# Mailchecker2.net
KiCad netlist of a schematic drawn in EAGLE
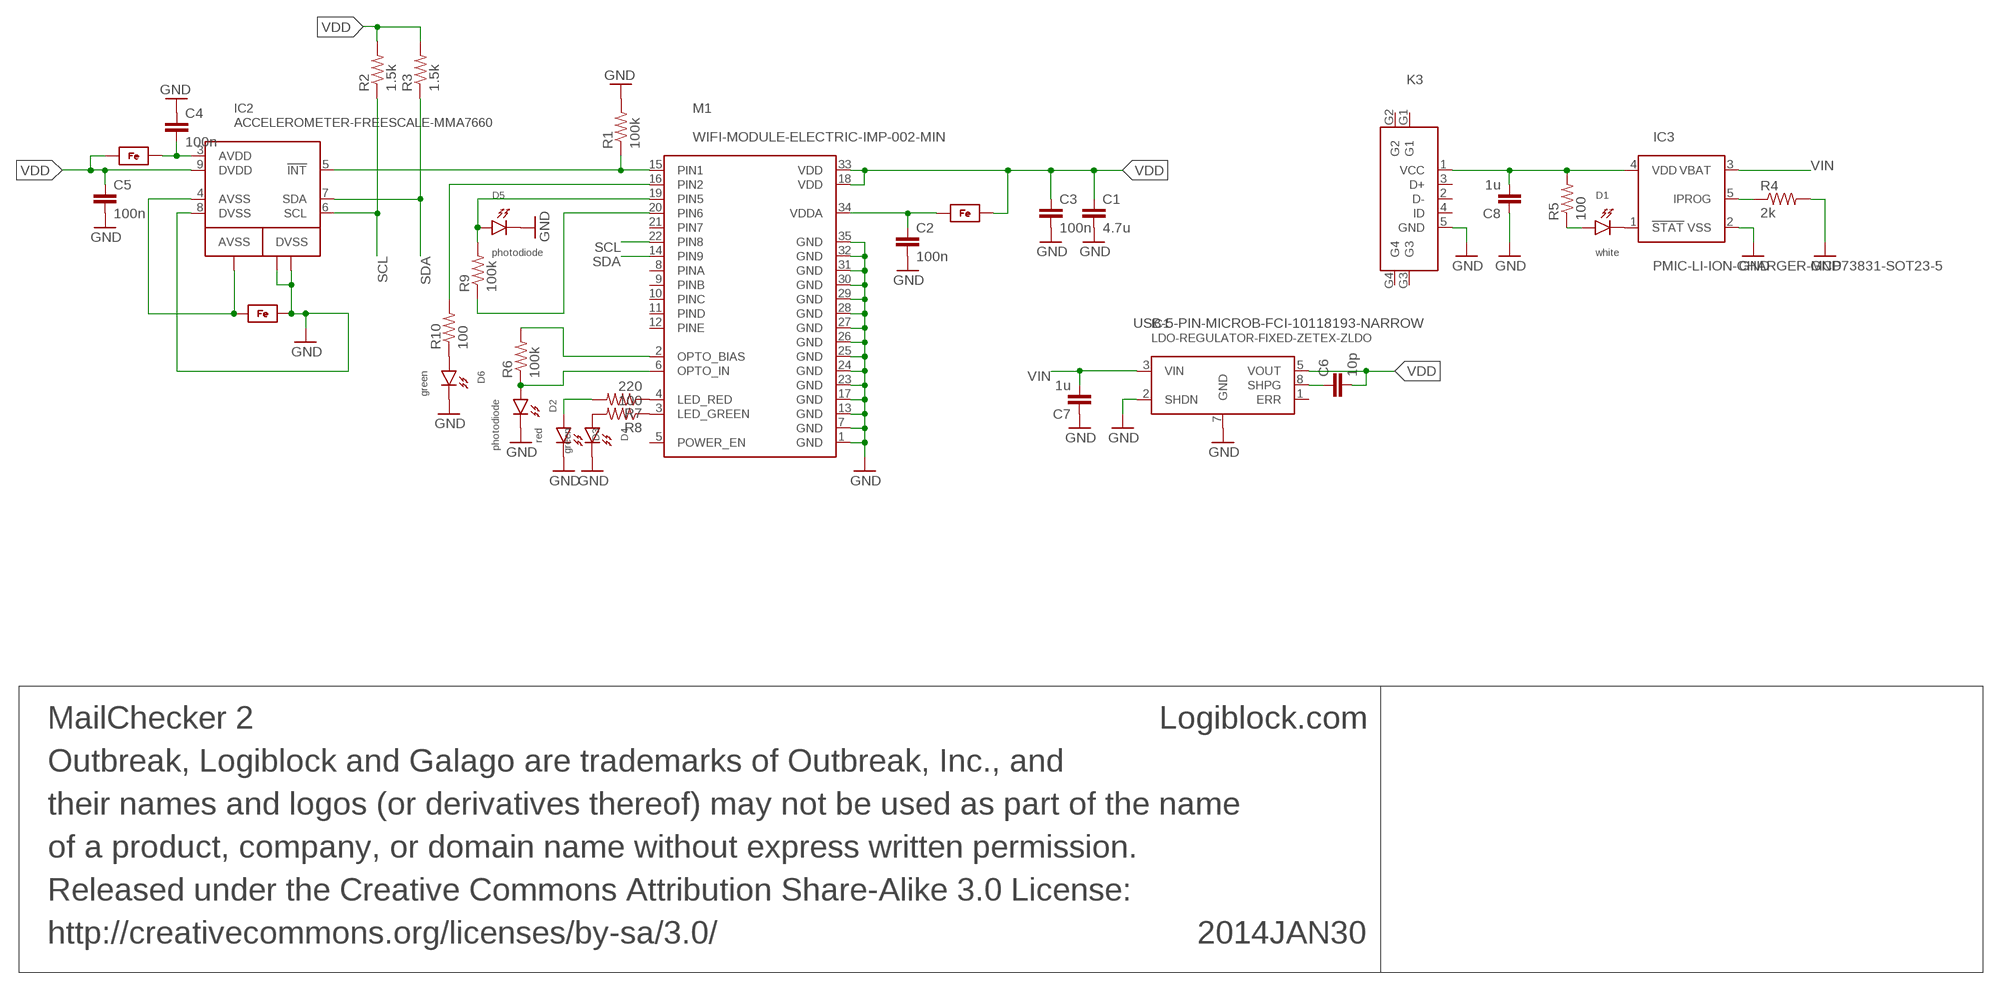
[diagram p0: schematic, sheet 1]

(export (version "E")
  (design (tool "Eeschema 10.0.6"))
  (components
    (comp (ref "2014JAN30")
      (value "MailChecker 2")
      (footprint "eagle-import:INFO-BLOCK")
      (libsource (lib "eagle-import") (part "INFO-BLOCK"))
    )
    (comp (ref "C1")
      (value "4.7u")
      (footprint "eagle-import:0805-MIN")
      (libsource (lib "eagle-import") (part "CAP-0805-MIN"))
    )
    (comp (ref "C2")
      (value "100n")
      (footprint "eagle-import:0402-MIN")
      (libsource (lib "eagle-import") (part "CAP-0402-MIN"))
    )
    (comp (ref "C3")
      (value "100n")
      (footprint "eagle-import:0402-MIN")
      (libsource (lib "eagle-import") (part "CAP-0402-MIN"))
    )
    (comp (ref "C4")
      (value "100n")
      (footprint "eagle-import:0402-MIN")
      (libsource (lib "eagle-import") (part "CAP-0402-MIN"))
    )
    (comp (ref "C5")
      (value "100n")
      (footprint "eagle-import:0402-MIN")
      (libsource (lib "eagle-import") (part "CAP-0402-MIN"))
    )
    (comp (ref "C6")
      (value "10p")
      (footprint "eagle-import:0402-MIN")
      (libsource (lib "eagle-import") (part "CAP-0402-MIN"))
    )
    (comp (ref "C7")
      (value "1u")
      (footprint "eagle-import:0603-MIN")
      (libsource (lib "eagle-import") (part "CAP-0603-MIN"))
    )
    (comp (ref "C8")
      (value "1u")
      (footprint "eagle-import:0603-MIN")
      (libsource (lib "eagle-import") (part "CAP-0603-MIN"))
    )
    (comp (ref "D1")
      (value "white")
      (footprint "eagle-import:0603-DIODE-MIN")
      (libsource (lib "eagle-import") (part "LED-0603-MIN"))
    )
    (comp (ref "D2")
      (value "photodiode")
      (footprint "eagle-import:0603-DIODE-MIN")
      (libsource (lib "eagle-import") (part "LED-0603-MIN"))
    )
    (comp (ref "D3")
      (value "red")
      (footprint "eagle-import:0603-DIODE-MIN")
      (libsource (lib "eagle-import") (part "LED-0603-MIN"))
    )
    (comp (ref "D4")
      (value "green")
      (footprint "eagle-import:0603-DIODE-MIN")
      (libsource (lib "eagle-import") (part "LED-0603-MIN"))
    )
    (comp (ref "D5")
      (value "photodiode")
      (footprint "eagle-import:0603-DIODE-MIN")
      (libsource (lib "eagle-import") (part "LED-0603-MIN"))
    )
    (comp (ref "D6")
      (value "green")
      (footprint "eagle-import:0603-DIODE-MIN")
      (libsource (lib "eagle-import") (part "LED-0603-MIN"))
    )
    (comp (ref "FB1")
      (value "FERRITE-BEAD-0603-MIN")
      (footprint "eagle-import:0603-MIN")
      (libsource (lib "eagle-import") (part "FERRITE-BEAD-0603-MIN"))
    )
    (comp (ref "FB2")
      (value "FERRITE-BEAD-0603-MIN")
      (footprint "eagle-import:0603-MIN")
      (libsource (lib "eagle-import") (part "FERRITE-BEAD-0603-MIN"))
    )
    (comp (ref "FB3")
      (value "FERRITE-BEAD-0603-MIN")
      (footprint "eagle-import:0603-MIN")
      (libsource (lib "eagle-import") (part "FERRITE-BEAD-0603-MIN"))
    )
    (comp (ref "IC1")
      (value "LDO-REGULATOR-FIXED-ZETEX-ZLDO")
      (footprint "eagle-import:SM8-ZETEX")
      (libsource (lib "eagle-import") (part "LDO-REGULATOR-FIXED-ZETEX-ZLDO"))
    )
    (comp (ref "IC2")
      (value "ACCELEROMETER-FREESCALE-MMA7660")
      (footprint "eagle-import:QFN10-3X3MM-FREESCALE-MMA7660")
      (libsource (lib "eagle-import") (part "ACCELEROMETER-FREESCALE-MMA7660"))
    )
    (comp (ref "IC3")
      (value "PMIC-LI-ION-CHARGER-MCP73831-SOT23-5")
      (footprint "eagle-import:SOT23-5")
      (libsource (lib "eagle-import") (part "PMIC-LI-ION-CHARGER-MCP73831-SOT23-5"))
    )
    (comp (ref "K3")
      (value "USB-5-PIN-MICROB-FCI-10118193-NARROW")
      (footprint "eagle-import:USB-MICROB-FCI-10118193-NARROW")
      (libsource (lib "eagle-import") (part "USB-5-PIN-MICROB-FCI-10118193-NARROW"))
    )
    (comp (ref "M1")
      (value "WIFI-MODULE-ELECTRIC-IMP-002-MIN")
      (footprint "eagle-import:ELECTRIC-IMP-002-MIN")
      (libsource (lib "eagle-import") (part "WIFI-MODULE-ELECTRIC-IMP-002-MIN"))
    )
    (comp (ref "R1")
      (value "100k")
      (footprint "eagle-import:0402-MIN")
      (libsource (lib "eagle-import") (part "RESISTOR-0402-MIN"))
    )
    (comp (ref "R2")
      (value "1.5k")
      (footprint "eagle-import:0402-MIN")
      (libsource (lib "eagle-import") (part "RESISTOR-0402-MIN"))
    )
    (comp (ref "R3")
      (value "1.5k")
      (footprint "eagle-import:0402-MIN")
      (libsource (lib "eagle-import") (part "RESISTOR-0402-MIN"))
    )
    (comp (ref "R4")
      (value "2k")
      (footprint "eagle-import:0402-MIN")
      (libsource (lib "eagle-import") (part "RESISTOR-0402-MIN"))
    )
    (comp (ref "R5")
      (value "100")
      (footprint "eagle-import:0402-MIN")
      (libsource (lib "eagle-import") (part "RESISTOR-0402-MIN"))
    )
    (comp (ref "R6")
      (value "100k")
      (footprint "eagle-import:0402-MIN")
      (libsource (lib "eagle-import") (part "RESISTOR-0402-MIN"))
    )
    (comp (ref "R7")
      (value "220")
      (footprint "eagle-import:0402-MIN")
      (libsource (lib "eagle-import") (part "RESISTOR-0402-MIN"))
    )
    (comp (ref "R8")
      (value "100")
      (footprint "eagle-import:0402-MIN")
      (libsource (lib "eagle-import") (part "RESISTOR-0402-MIN"))
    )
    (comp (ref "R9")
      (value "100k")
      (footprint "eagle-import:0402-MIN")
      (libsource (lib "eagle-import") (part "RESISTOR-0402-MIN"))
    )
    (comp (ref "R10")
      (value "100")
      (footprint "eagle-import:0402-MIN")
      (libsource (lib "eagle-import") (part "RESISTOR-0402-MIN"))
    )
  )
  (nets
    (net (code "1") (name "/SCL") (class "Default")
      (node (ref "IC2") (pin "6") (pinfunction "SCL_6") (pintype "bidirectional"))
      (node (ref "M1") (pin "22") (pinfunction "PIN8_22") (pintype "bidirectional"))
      (node (ref "R2") (pin "1") (pinfunction "1_1") (pintype "passive"))
    )
    (net (code "2") (name "/SDA") (class "Default")
      (node (ref "IC2") (pin "7") (pinfunction "SDA_7") (pintype "bidirectional"))
      (node (ref "M1") (pin "14") (pinfunction "PIN9_14") (pintype "bidirectional"))
      (node (ref "R3") (pin "1") (pinfunction "1_1") (pintype "passive"))
    )
    (net (code "3") (name "/VIN") (class "Default")
      (node (ref "C7") (pin "1") (pinfunction "1_1") (pintype "bidirectional"))
      (node (ref "IC1") (pin "3") (pinfunction "VIN_3") (pintype "bidirectional"))
      (node (ref "IC3") (pin "3") (pinfunction "VBAT_3") (pintype "bidirectional"))
    )
    (net (code "4") (name "GND") (class "Default")
      (node (ref "C1") (pin "1") (pinfunction "1_1") (pintype "bidirectional"))
      (node (ref "C2") (pin "1") (pinfunction "1_1") (pintype "bidirectional"))
      (node (ref "C3") (pin "1") (pinfunction "1_1") (pintype "bidirectional"))
      (node (ref "C4") (pin "2") (pinfunction "2_2") (pintype "bidirectional"))
      (node (ref "C5") (pin "1") (pinfunction "1_1") (pintype "bidirectional"))
      (node (ref "C7") (pin "2") (pinfunction "2_2") (pintype "bidirectional"))
      (node (ref "C8") (pin "2") (pinfunction "2_2") (pintype "bidirectional"))
      (node (ref "D2") (pin "K") (pinfunction "K_K") (pintype "bidirectional"))
      (node (ref "D3") (pin "K") (pinfunction "K_K") (pintype "bidirectional"))
      (node (ref "D4") (pin "K") (pinfunction "K_K") (pintype "bidirectional"))
      (node (ref "D5") (pin "K") (pinfunction "K_K") (pintype "bidirectional"))
      (node (ref "D6") (pin "K") (pinfunction "K_K") (pintype "bidirectional"))
      (node (ref "FB2") (pin "2") (pinfunction "2_2") (pintype "bidirectional"))
      (node (ref "IC1") (pin "2") (pinfunction "SHDN_2") (pintype "bidirectional"))
      (node (ref "IC1") (pin "7") (pinfunction "GND_7") (pintype "bidirectional"))
      (node (ref "IC2") (pin "8") (pinfunction "DVSS_8") (pintype "bidirectional"))
      (node (ref "IC2") (pin "G1") (pinfunction "G1_G1") (pintype "bidirectional"))
      (node (ref "IC2") (pin "G2") (pinfunction "G2_G2") (pintype "bidirectional"))
      (node (ref "IC3") (pin "2") (pinfunction "VSS_2") (pintype "bidirectional"))
      (node (ref "K3") (pin "5") (pinfunction "GND_5") (pintype "bidirectional"))
      (node (ref "M1") (pin "1") (pinfunction "GND_1") (pintype "bidirectional"))
      (node (ref "M1") (pin "13") (pinfunction "GND_13") (pintype "bidirectional"))
      (node (ref "M1") (pin "17") (pinfunction "GND_17") (pintype "bidirectional"))
      (node (ref "M1") (pin "23") (pinfunction "GND_23") (pintype "bidirectional"))
      (node (ref "M1") (pin "24") (pinfunction "GND_24") (pintype "bidirectional"))
      (node (ref "M1") (pin "25") (pinfunction "GND_25") (pintype "bidirectional"))
      (node (ref "M1") (pin "26") (pinfunction "GND_26") (pintype "bidirectional"))
      (node (ref "M1") (pin "27") (pinfunction "GND_27") (pintype "bidirectional"))
      (node (ref "M1") (pin "28") (pinfunction "GND_28") (pintype "bidirectional"))
      (node (ref "M1") (pin "29") (pinfunction "GND_29") (pintype "bidirectional"))
      (node (ref "M1") (pin "30") (pinfunction "GND_30") (pintype "bidirectional"))
      (node (ref "M1") (pin "31") (pinfunction "GND_31") (pintype "bidirectional"))
      (node (ref "M1") (pin "32") (pinfunction "GND_32") (pintype "bidirectional"))
      (node (ref "M1") (pin "35") (pinfunction "GND_35") (pintype "bidirectional"))
      (node (ref "M1") (pin "7") (pinfunction "GND_7") (pintype "bidirectional"))
      (node (ref "R1") (pin "2") (pinfunction "2_2") (pintype "passive"))
      (node (ref "R4") (pin "2") (pinfunction "2_2") (pintype "passive"))
    )
    (net (code "5") (name "Net-(D1-PadA)") (class "Default")
      (node (ref "D1") (pin "A") (pinfunction "A_A") (pintype "bidirectional"))
      (node (ref "R5") (pin "1") (pinfunction "1_1") (pintype "passive"))
    )
    (net (code "6") (name "Net-(D3-PadA)") (class "Default")
      (node (ref "D3") (pin "A") (pinfunction "A_A") (pintype "bidirectional"))
      (node (ref "R7") (pin "2") (pinfunction "2_2") (pintype "passive"))
    )
    (net (code "7") (name "Net-(D4-PadA)") (class "Default")
      (node (ref "D4") (pin "A") (pinfunction "A_A") (pintype "bidirectional"))
      (node (ref "R8") (pin "2") (pinfunction "2_2") (pintype "passive"))
    )
    (net (code "8") (name "Net-(D6-PadA)") (class "Default")
      (node (ref "D6") (pin "A") (pinfunction "A_A") (pintype "bidirectional"))
      (node (ref "R10") (pin "1") (pinfunction "1_1") (pintype "passive"))
    )
    (net (code "9") (name "Net-(IC1-SHPG)") (class "Default")
      (node (ref "C6") (pin "2") (pinfunction "2_2") (pintype "bidirectional"))
      (node (ref "IC1") (pin "8") (pinfunction "SHPG_8") (pintype "bidirectional"))
    )
    (net (code "10") (name "Net-(IC2-AVDD)") (class "Default")
      (node (ref "C4") (pin "1") (pinfunction "1_1") (pintype "bidirectional"))
      (node (ref "FB3") (pin "2") (pinfunction "2_2") (pintype "bidirectional"))
      (node (ref "IC2") (pin "3") (pinfunction "AVDD_3") (pintype "bidirectional"))
    )
    (net (code "11") (name "Net-(IC2-AVSS)") (class "Default")
      (node (ref "FB2") (pin "1") (pinfunction "1_1") (pintype "bidirectional"))
      (node (ref "IC2") (pin "1") (pinfunction "G3_1") (pintype "bidirectional"))
      (node (ref "IC2") (pin "4") (pinfunction "AVSS_4") (pintype "bidirectional"))
    )
    (net (code "12") (name "Net-(IC2-~{INT})") (class "Default")
      (node (ref "IC2") (pin "5") (pinfunction "~{INT}_5") (pintype "bidirectional"))
      (node (ref "M1") (pin "15") (pinfunction "PIN1_15") (pintype "bidirectional"))
      (node (ref "R1") (pin "1") (pinfunction "1_1") (pintype "passive"))
    )
    (net (code "13") (name "Net-(IC3-IPROG)") (class "Default")
      (node (ref "IC3") (pin "5") (pinfunction "IPROG_5") (pintype "bidirectional"))
      (node (ref "R4") (pin "1") (pinfunction "1_1") (pintype "passive"))
    )
    (net (code "14") (name "Net-(IC3-VDD)") (class "Default")
      (node (ref "C8") (pin "1") (pinfunction "1_1") (pintype "bidirectional"))
      (node (ref "IC3") (pin "4") (pinfunction "VDD_4") (pintype "bidirectional"))
      (node (ref "K3") (pin "1") (pinfunction "VCC_1") (pintype "bidirectional"))
      (node (ref "R5") (pin "2") (pinfunction "2_2") (pintype "passive"))
    )
    (net (code "15") (name "Net-(IC3-~{STAT})") (class "Default")
      (node (ref "D1") (pin "K") (pinfunction "K_K") (pintype "bidirectional"))
      (node (ref "IC3") (pin "1") (pinfunction "~{STAT}_1") (pintype "bidirectional"))
    )
    (net (code "16") (name "Net-(M1-LED_GREEN)") (class "Default")
      (node (ref "M1") (pin "3") (pinfunction "LED_GREEN_3") (pintype "bidirectional"))
      (node (ref "R8") (pin "1") (pinfunction "1_1") (pintype "passive"))
    )
    (net (code "17") (name "Net-(M1-LED_RED)") (class "Default")
      (node (ref "M1") (pin "4") (pinfunction "LED_RED_4") (pintype "bidirectional"))
      (node (ref "R7") (pin "1") (pinfunction "1_1") (pintype "passive"))
    )
    (net (code "18") (name "Net-(M1-OPTO_BIAS)") (class "Default")
      (node (ref "M1") (pin "2") (pinfunction "OPTO_BIAS_2") (pintype "bidirectional"))
      (node (ref "R6") (pin "2") (pinfunction "2_2") (pintype "passive"))
    )
    (net (code "19") (name "Net-(M1-OPTO_IN)") (class "Default")
      (node (ref "D2") (pin "A") (pinfunction "A_A") (pintype "bidirectional"))
      (node (ref "M1") (pin "6") (pinfunction "OPTO_IN_6") (pintype "bidirectional"))
      (node (ref "R6") (pin "1") (pinfunction "1_1") (pintype "passive"))
    )
    (net (code "20") (name "Net-(M1-PIN2)") (class "Default")
      (node (ref "M1") (pin "16") (pinfunction "PIN2_16") (pintype "bidirectional"))
      (node (ref "R10") (pin "2") (pinfunction "2_2") (pintype "passive"))
    )
    (net (code "21") (name "Net-(M1-PIN5)") (class "Default")
      (node (ref "D5") (pin "A") (pinfunction "A_A") (pintype "bidirectional"))
      (node (ref "M1") (pin "19") (pinfunction "PIN5_19") (pintype "bidirectional"))
      (node (ref "R9") (pin "2") (pinfunction "2_2") (pintype "passive"))
    )
    (net (code "22") (name "Net-(M1-PIN6)") (class "Default")
      (node (ref "M1") (pin "20") (pinfunction "PIN6_20") (pintype "bidirectional"))
      (node (ref "R9") (pin "1") (pinfunction "1_1") (pintype "passive"))
    )
    (net (code "23") (name "Net-(M1-VDDA)") (class "Default")
      (node (ref "C2") (pin "2") (pinfunction "2_2") (pintype "bidirectional"))
      (node (ref "FB1") (pin "1") (pinfunction "1_1") (pintype "bidirectional"))
      (node (ref "M1") (pin "34") (pinfunction "VDDA_34") (pintype "bidirectional"))
    )
    (net (code "24") (name "VDD") (class "Default")
      (node (ref "C1") (pin "2") (pinfunction "2_2") (pintype "bidirectional"))
      (node (ref "C3") (pin "2") (pinfunction "2_2") (pintype "bidirectional"))
      (node (ref "C5") (pin "2") (pinfunction "2_2") (pintype "bidirectional"))
      (node (ref "C6") (pin "1") (pinfunction "1_1") (pintype "bidirectional"))
      (node (ref "FB1") (pin "2") (pinfunction "2_2") (pintype "bidirectional"))
      (node (ref "FB3") (pin "1") (pinfunction "1_1") (pintype "bidirectional"))
      (node (ref "IC1") (pin "5") (pinfunction "VOUT_5") (pintype "bidirectional"))
      (node (ref "IC2") (pin "9") (pinfunction "DVDD_9") (pintype "bidirectional"))
      (node (ref "M1") (pin "18") (pinfunction "VDD_18") (pintype "bidirectional"))
      (node (ref "M1") (pin "33") (pinfunction "VDD_33") (pintype "bidirectional"))
      (node (ref "R2") (pin "2") (pinfunction "2_2") (pintype "passive"))
      (node (ref "R3") (pin "2") (pinfunction "2_2") (pintype "passive"))
    )
    (net (code "25") (name "unconnected-(IC1-ERR-Pad1)") (class "Default")
      (node (ref "IC1") (pin "1") (pinfunction "ERR_1") (pintype "bidirectional"))
    )
    (net (code "26") (name "unconnected-(K3-D+-Pad3)") (class "Default")
      (node (ref "K3") (pin "3") (pinfunction "D+_3") (pintype "bidirectional"))
    )
    (net (code "27") (name "unconnected-(K3-D--Pad2)") (class "Default")
      (node (ref "K3") (pin "2") (pinfunction "D-_2") (pintype "bidirectional"))
    )
    (net (code "28") (name "unconnected-(K3-ID-Pad4)") (class "Default")
      (node (ref "K3") (pin "4") (pinfunction "ID_4") (pintype "bidirectional"))
    )
    (net (code "29") (name "unconnected-(K3-PadG1)") (class "Default")
      (node (ref "K3") (pin "G1") (pinfunction "G1_G1") (pintype "bidirectional"))
    )
    (net (code "30") (name "unconnected-(K3-PadG2)") (class "Default")
      (node (ref "K3") (pin "G2") (pinfunction "G2_G2") (pintype "bidirectional"))
    )
    (net (code "31") (name "unconnected-(K3-PadG3)") (class "Default")
      (node (ref "K3") (pin "G3") (pinfunction "G3_G3") (pintype "bidirectional"))
    )
    (net (code "32") (name "unconnected-(K3-PadG4)") (class "Default")
      (node (ref "K3") (pin "G4") (pinfunction "G4_G4") (pintype "bidirectional"))
    )
    (net (code "33") (name "unconnected-(M1-PIN7-Pad21)") (class "Default")
      (node (ref "M1") (pin "21") (pinfunction "PIN7_21") (pintype "bidirectional"))
    )
    (net (code "34") (name "unconnected-(M1-PINA-Pad8)") (class "Default")
      (node (ref "M1") (pin "8") (pinfunction "PINA_8") (pintype "bidirectional"))
    )
    (net (code "35") (name "unconnected-(M1-PINB-Pad9)") (class "Default")
      (node (ref "M1") (pin "9") (pinfunction "PINB_9") (pintype "bidirectional"))
    )
    (net (code "36") (name "unconnected-(M1-PINC-Pad10)") (class "Default")
      (node (ref "M1") (pin "10") (pinfunction "PINC_10") (pintype "bidirectional"))
    )
    (net (code "37") (name "unconnected-(M1-PIND-Pad11)") (class "Default")
      (node (ref "M1") (pin "11") (pinfunction "PIND_11") (pintype "bidirectional"))
    )
    (net (code "38") (name "unconnected-(M1-PINE-Pad12)") (class "Default")
      (node (ref "M1") (pin "12") (pinfunction "PINE_12") (pintype "bidirectional"))
    )
    (net (code "39") (name "unconnected-(M1-POWER_EN-Pad5)") (class "Default")
      (node (ref "M1") (pin "5") (pinfunction "POWER_EN_5") (pintype "bidirectional"))
    )
  )
)
